# CE_BJTInfineonTSFP-4-1_Simple_v1.net
KiCad netlist of a schematic drawn in Altium Designer
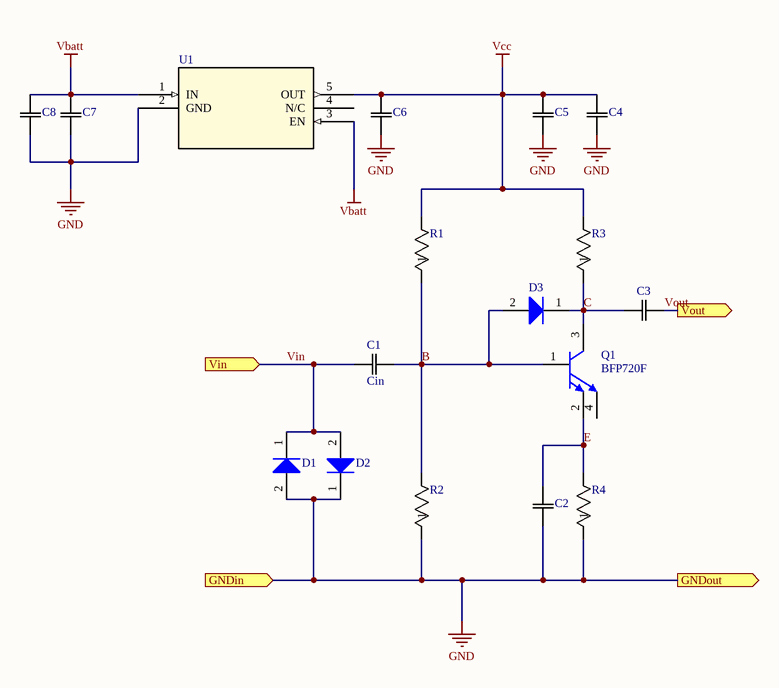
[diagram p0: CE_BJTInfineonTSFP-4-1_Simple_v1.SchDoc]

(export (version "E")
  (design (tool "Eeschema 10.0.6"))
  (components
    (comp (ref "C1")
      (value "Cin")
      (footprint "C0201")
      (description "No Description Available")
      (fields
        (field (name "MANUFACTURER_PART_NUMBER") "C0201C270J3GACTU")
        (field (name "COPYRIGHT") "Copyright (C) 2018 Accelerated Designs. All rights reserved")
      )
      (libsource (lib "0201Capacitor_Yageo") (part "C0201C270J3GACTU"))
    )
    (comp (ref "C2")
      (value "~")
      (footprint "C0201")
      (description "No Description Available")
      (fields
        (field (name "MANUFACTURER_PART_NUMBER") "C0201C270J3GACTU")
        (field (name "COPYRIGHT") "Copyright (C) 2018 Accelerated Designs. All rights reserved")
      )
      (libsource (lib "0201Capacitor_Yageo") (part "C0201C270J3GACTU"))
    )
    (comp (ref "C3")
      (value "~")
      (footprint "C0201")
      (description "No Description Available")
      (fields
        (field (name "MANUFACTURER_PART_NUMBER") "C0201C270J3GACTU")
        (field (name "COPYRIGHT") "Copyright (C) 2018 Accelerated Designs. All rights reserved")
      )
      (libsource (lib "0201Capacitor_Yageo") (part "C0201C270J3GACTU"))
    )
    (comp (ref "C4")
      (value "~")
      (footprint "CAP_CBR_0201")
      (description "No Description Available")
      (fields
        (field (name "MANUFACTURER_PART_NUMBER") "CBR02C399C3GAC")
        (field (name "COPYRIGHT") "Copyright (C) 2018 Accelerated Designs. All rights reserved")
      )
      (libsource (lib "0201Capacitor_KEMET") (part "CBR02C399C3GAC"))
    )
    (comp (ref "C5")
      (value "~")
      (footprint "CAP_CBR_0201")
      (description "No Description Available")
      (fields
        (field (name "MANUFACTURER_PART_NUMBER") "CBR02C399C3GAC")
        (field (name "COPYRIGHT") "Copyright (C) 2018 Accelerated Designs. All rights reserved")
      )
      (libsource (lib "0201Capacitor_KEMET") (part "CBR02C399C3GAC"))
    )
    (comp (ref "C6")
      (value "~")
      (footprint "YAG_CC0402")
      (description "No Description Available")
      (fields
        (field (name "MANUFACTURER_PART_NUMBER") "CC0402KRX7R9BB103")
        (field (name "COPYRIGHT") "Copyright (C) 2018 Accelerated Designs. All rights reserved")
      )
      (libsource (lib "0402Capacitor_Yageo") (part "CC0402KRX7R9BB10"))
    )
    (comp (ref "C7")
      (value "~")
      (footprint "YAG_CC0402")
      (description "No Description Available")
      (fields
        (field (name "MANUFACTURER_PART_NUMBER") "CC0402KRX7R9BB103")
        (field (name "COPYRIGHT") "Copyright (C) 2018 Accelerated Designs. All rights reserved")
      )
      (libsource (lib "0402Capacitor_Yageo") (part "CC0402KRX7R9BB10"))
    )
    (comp (ref "C8")
      (value "~")
      (footprint "YAG_CC0402")
      (description "No Description Available")
      (fields
        (field (name "MANUFACTURER_PART_NUMBER") "CC0402KRX7R9BB103")
        (field (name "COPYRIGHT") "Copyright (C) 2018 Accelerated Designs. All rights reserved")
      )
      (libsource (lib "0402Capacitor_Yageo") (part "CC0402KRX7R9BB10"))
    )
    (comp (ref "D1")
      (value "~")
      (footprint "INF-SOD323_V")
      (description "Single Silicon Schottky Diode, 110 mA IF Max, SOD32, Green")
      (fields (field (name "MANUFACTURER") "Infineon") (field (name "PARTNUMBER") "BAT15-03W"))
      (libsource (lib "Infineon_RFSchottkyDiode_SOD323") (part "BAT15-03W"))
    )
    (comp (ref "D2")
      (value "~")
      (footprint "INF-SOD323_V")
      (description "Single Silicon Schottky Diode, 110 mA IF Max, SOD32, Green")
      (fields (field (name "MANUFACTURER") "Infineon") (field (name "PARTNUMBER") "BAT15-03W"))
      (libsource (lib "Infineon_RFSchottkyDiode_SOD323") (part "BAT15-03W"))
    )
    (comp (ref "D3")
      (value "~")
      (footprint "INF-SOD323_V")
      (description "Single Silicon Schottky Diode, 110 mA IF Max, SOD32, Green")
      (fields (field (name "MANUFACTURER") "Infineon") (field (name "PARTNUMBER") "BAT15-03W"))
      (libsource (lib "Infineon_RFSchottkyDiode_SOD323") (part "BAT15-03W"))
    )
    (comp (ref "Q1")
      (value "BFP720F")
      (footprint "INF-TSFP-4-1_V")
      (fields (field (name "MANUFACTURER") "Infineon"))
      (libsource (lib "Infineon_RFBJT_TSFP-4-1") (part "BFP720F"))
    )
    (comp (ref "R1")
      (value "~")
      (footprint "RES_RC0201_P6XP3")
      (description "No Description Available")
      (fields
        (field (name "MANUFACTURER_PART_NUMBER") "RC0201FR-0718KL")
        (field (name "COPYRIGHT") "Copyright (C) 2018 Accelerated Designs. All rights reserved")
      )
      (libsource (lib "0201Resistor_Yageo") (part "RC0201FR-0718KL"))
    )
    (comp (ref "R2")
      (value "~")
      (footprint "RES_RC0201_P6XP3")
      (description "No Description Available")
      (fields
        (field (name "MANUFACTURER_PART_NUMBER") "RC0201FR-0718KL")
        (field (name "COPYRIGHT") "Copyright (C) 2018 Accelerated Designs. All rights reserved")
      )
      (libsource (lib "0201Resistor_Yageo") (part "RC0201FR-0718KL"))
    )
    (comp (ref "R3")
      (value "~")
      (footprint "RES_RC0201_P6XP3")
      (description "No Description Available")
      (fields
        (field (name "MANUFACTURER_PART_NUMBER") "RC0201FR-0718KL")
        (field (name "COPYRIGHT") "Copyright (C) 2018 Accelerated Designs. All rights reserved")
      )
      (libsource (lib "0201Resistor_Yageo") (part "RC0201FR-0718KL"))
    )
    (comp (ref "R4")
      (value "~")
      (footprint "RES_RC0201_P6XP3")
      (description "No Description Available")
      (fields
        (field (name "MANUFACTURER_PART_NUMBER") "RC0201FR-0718KL")
        (field (name "COPYRIGHT") "Copyright (C) 2018 Accelerated Designs. All rights reserved")
      )
      (libsource (lib "0201Resistor_Yageo") (part "RC0201FR-0718KL"))
    )
    (comp (ref "U1")
      (value "~")
      (footprint "DBV5")
      (description "No Description Available")
      (fields
        (field (name "MANUFACTURER_PART_NUMBER") "LP5907MFX-3.3/NOPB")
        (field (name "COPYRIGHT") "Copyright (C) 2018 Accelerated Designs. All rights reserved")
      )
      (libsource (lib "TI_LDO_3V3_SOT325") (part "LP5907MFX-3.3/NO"))
    )
  )
  (nets
    (net (code "1") (name "/B") (class "Default")
      (node (ref "C1") (pin "2") (pinfunction "2_2") (pintype "passive"))
      (node (ref "D3") (pin "2") (pinfunction "A_2") (pintype "passive"))
      (node (ref "Q1") (pin "1") (pinfunction "B_1") (pintype "passive"))
      (node (ref "R1") (pin "1") (pinfunction "1_1") (pintype "passive"))
      (node (ref "R2") (pin "2") (pinfunction "2_2") (pintype "passive"))
    )
    (net (code "2") (name "/C") (class "Default")
      (node (ref "C3") (pin "1") (pinfunction "1_1") (pintype "passive"))
      (node (ref "D3") (pin "1") (pinfunction "K_1") (pintype "passive"))
      (node (ref "Q1") (pin "3") (pinfunction "C_3") (pintype "passive"))
      (node (ref "R3") (pin "1") (pinfunction "1_1") (pintype "passive"))
    )
    (net (code "3") (name "/E") (class "Default")
      (node (ref "C2") (pin "2") (pinfunction "2_2") (pintype "passive"))
      (node (ref "Q1") (pin "2") (pinfunction "E_2") (pintype "passive"))
      (node (ref "R4") (pin "2") (pinfunction "2_2") (pintype "passive"))
    )
    (net (code "4") (name "/Vin") (class "Default")
      (node (ref "C1") (pin "1") (pinfunction "1_1") (pintype "passive"))
      (node (ref "D1") (pin "1") (pinfunction "K_1") (pintype "passive"))
      (node (ref "D2") (pin "2") (pinfunction "A_2") (pintype "passive"))
    )
    (net (code "5") (name "/Vout") (class "Default")
      (node (ref "C3") (pin "2") (pinfunction "2_2") (pintype "passive"))
    )
    (net (code "6") (name "GND") (class "Default")
      (node (ref "C2") (pin "1") (pinfunction "1_1") (pintype "passive"))
      (node (ref "C4") (pin "1") (pinfunction "1_1") (pintype "passive"))
      (node (ref "C5") (pin "1") (pinfunction "1_1") (pintype "passive"))
      (node (ref "C6") (pin "1") (pinfunction "1_1") (pintype "passive"))
      (node (ref "C7") (pin "1") (pinfunction "1_1") (pintype "passive"))
      (node (ref "C8") (pin "1") (pinfunction "1_1") (pintype "passive"))
      (node (ref "D1") (pin "2") (pinfunction "A_2") (pintype "passive"))
      (node (ref "D2") (pin "1") (pinfunction "K_1") (pintype "passive"))
      (node (ref "R2") (pin "1") (pinfunction "1_1") (pintype "passive"))
      (node (ref "R4") (pin "1") (pinfunction "1_1") (pintype "passive"))
      (node (ref "U1") (pin "2") (pinfunction "GND_2") (pintype "power_in"))
    )
    (net (code "7") (name "Vbatt") (class "Default")
      (node (ref "C7") (pin "2") (pinfunction "2_2") (pintype "passive"))
      (node (ref "C8") (pin "2") (pinfunction "2_2") (pintype "passive"))
      (node (ref "U1") (pin "1") (pinfunction "IN_1") (pintype "input"))
      (node (ref "U1") (pin "3") (pinfunction "EN_3") (pintype "input"))
    )
    (net (code "8") (name "Vcc") (class "Default")
      (node (ref "C4") (pin "2") (pinfunction "2_2") (pintype "passive"))
      (node (ref "C5") (pin "2") (pinfunction "2_2") (pintype "passive"))
      (node (ref "C6") (pin "2") (pinfunction "2_2") (pintype "passive"))
      (node (ref "R1") (pin "2") (pinfunction "2_2") (pintype "passive"))
      (node (ref "R3") (pin "2") (pinfunction "2_2") (pintype "passive"))
      (node (ref "U1") (pin "5") (pinfunction "OUT_5") (pintype "output"))
    )
    (net (code "9") (name "unconnected-(Q1-E-Pad4)") (class "Default")
      (node (ref "Q1") (pin "4") (pinfunction "E_4") (pintype "passive"))
    )
    (net (code "10") (name "unconnected-(U1-N{slash}C-Pad4)") (class "Default")
      (node (ref "U1") (pin "4") (pinfunction "N/C_4") (pintype "passive"))
    )
  )
)
